# MCU.net
KiCad netlist of a schematic drawn in Altium Designer
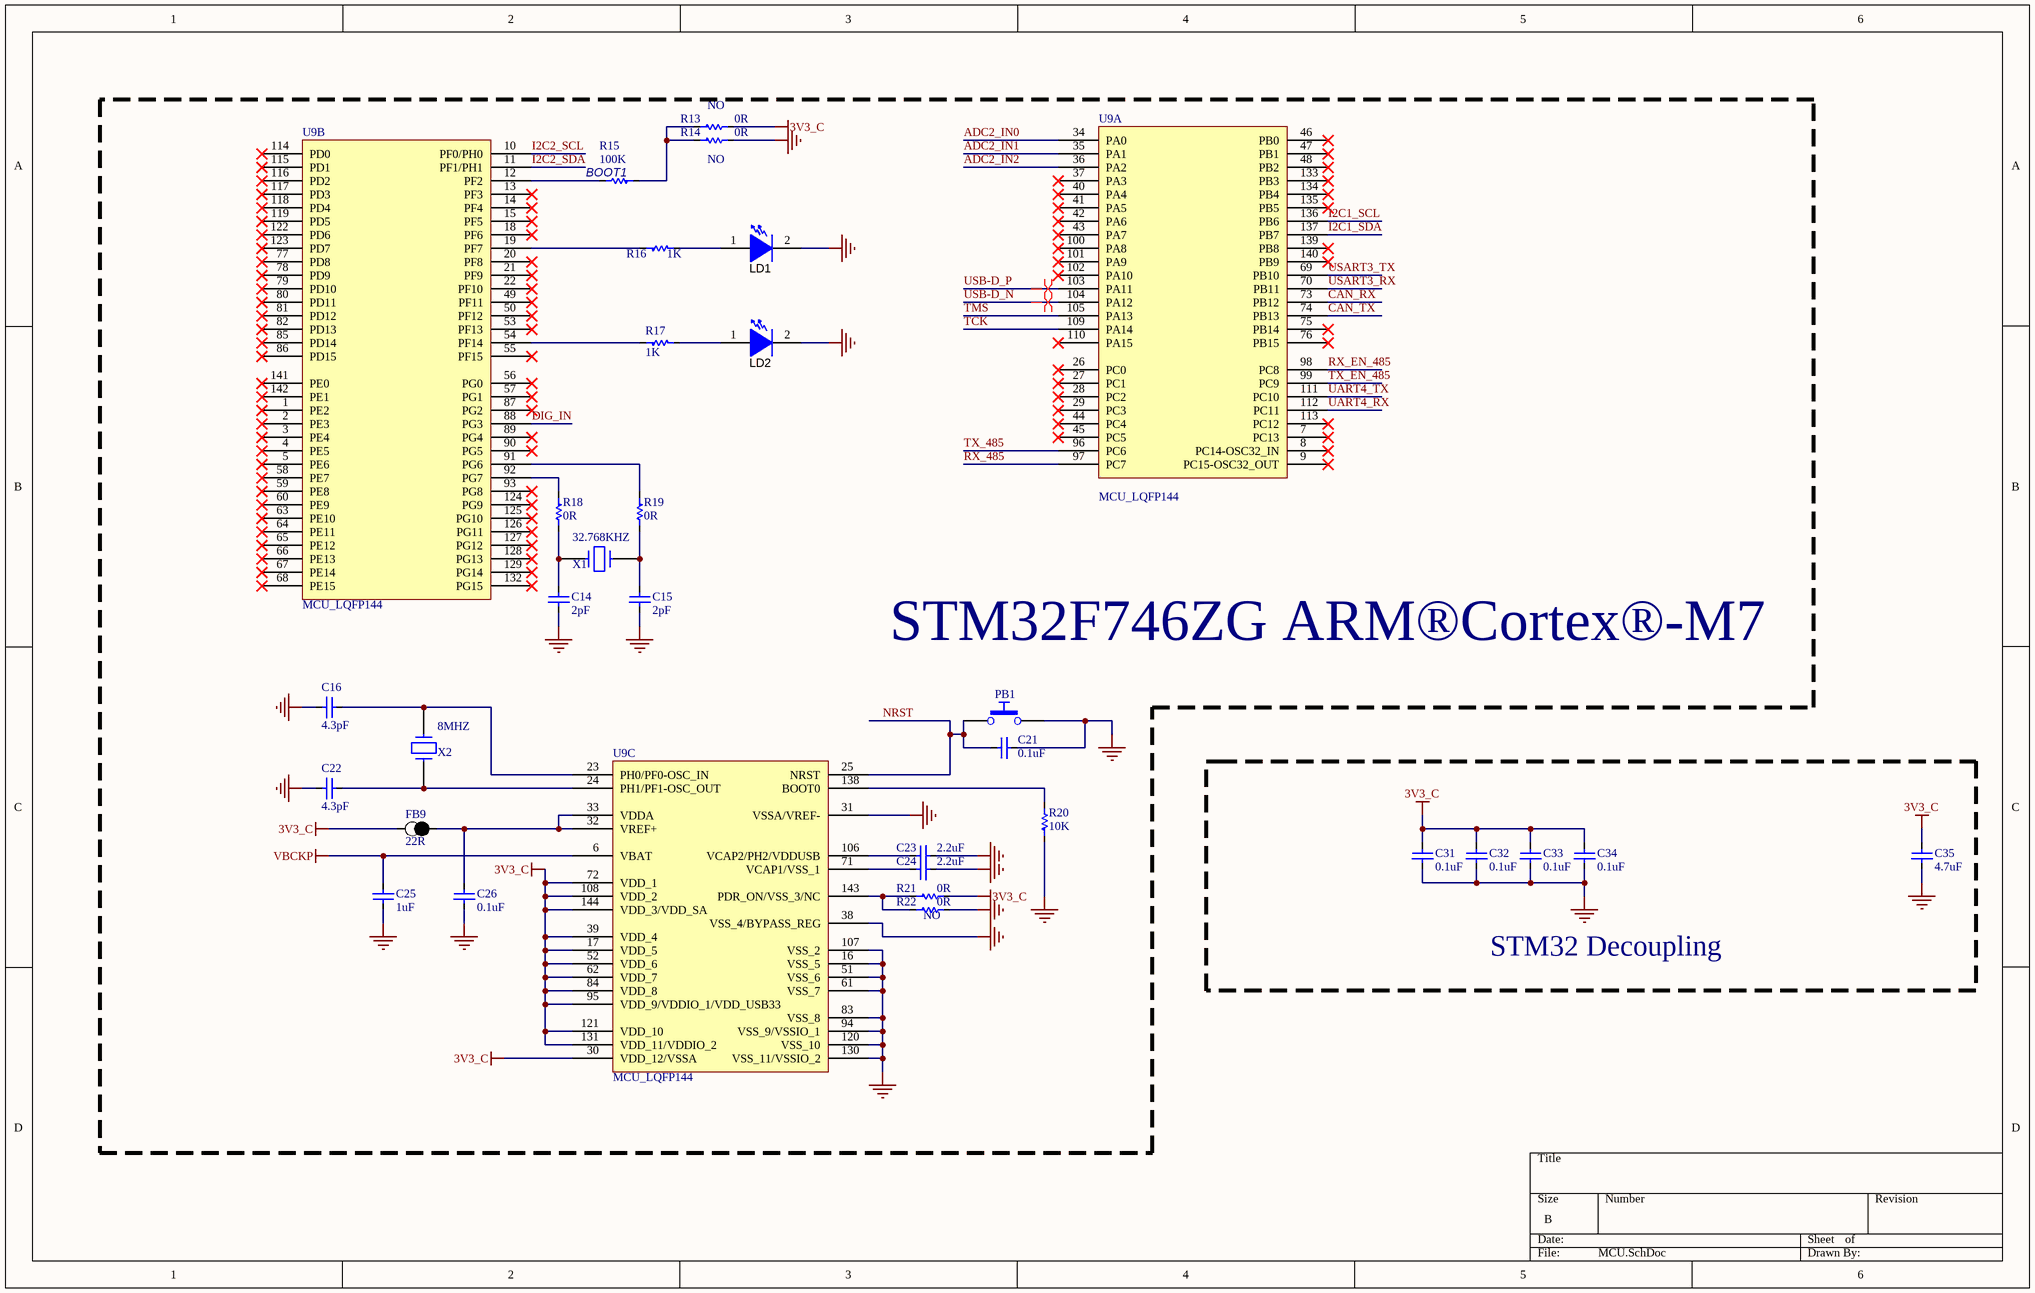
[diagram p0: MCU.SchDoc]

(export (version "E")
  (design (tool "Eeschema 10.0.6"))
  (components
    (comp (ref "C14")
      (value "2pF")
      (footprint "CAPC1608-0603X85N")
      (description "CAP CER 2PF 50V NPO 0603")
      (fields (field (name "MANUFACTURER") "Yageo") (field (name "VOLTAGE") "50V"))
      (libsource (lib "capacitor") (part "Capacitor Ceramic"))
    )
    (comp (ref "C15")
      (value "2pF")
      (footprint "CAPC1608-0603X85N")
      (description "CAP CER 2PF 50V NPO 0603")
      (fields (field (name "MANUFACTURER") "Yageo") (field (name "VOLTAGE") "50V"))
      (libsource (lib "capacitor") (part "Capacitor Ceramic"))
    )
    (comp (ref "C16")
      (value "4.3pF")
      (footprint "CAPC1005-0402X55N")
      (description "CAP CER 4.3PF 50V C0G/NPO 0402")
      (fields (field (name "MANUFACTURER") "Yageo") (field (name "VOLTAGE") "50V"))
      (libsource (lib "capacitor") (part "Capacitor Ceramic"))
    )
    (comp (ref "C21")
      (value "0.1uF")
      (footprint "CAPC1608-0603X85N")
      (description "CAP CER 0.1UF 25V X7R 0603")
      (fields (field (name "MANUFACTURER") "Yageo") (field (name "VOLTAGE") "25V"))
      (libsource (lib "capacitor") (part "Capacitor Ceramic"))
    )
    (comp (ref "C22")
      (value "4.3pF")
      (footprint "CAPC1005-0402X55N")
      (description "CAP CER 4.3PF 50V C0G/NPO 0402")
      (fields (field (name "MANUFACTURER") "Yageo") (field (name "VOLTAGE") "50V"))
      (libsource (lib "capacitor") (part "Capacitor Ceramic"))
    )
    (comp (ref "C23")
      (value "2.2uF")
      (footprint "CAPC2012-0805X80N")
      (description "CAP CER 2.2UF 16V X7R 0805")
      (fields (field (name "VOLTAGE") "16V") (field (name "TOLERANCE") "±10%"))
      (libsource (lib "capacitor") (part "Capacitor Ceramic"))
    )
    (comp (ref "C24")
      (value "2.2uF")
      (footprint "CAPC2012-0805X80N")
      (description "CAP CER 2.2UF 16V X7R 0805")
      (fields (field (name "VOLTAGE") "16V") (field (name "TOLERANCE") "±10%"))
      (libsource (lib "capacitor") (part "Capacitor Ceramic"))
    )
    (comp (ref "C25")
      (value "1uF")
      (footprint "CAPC1608-0603X85N")
      (description "CAP CER 1UF 25V X5R 0603")
      (fields (field (name "MANUFACTURER") "Samsung Electro-Mechanics") (field (name "VOLTAGE") "25V"))
      (libsource (lib "capacitor") (part "Capacitor Ceramic"))
    )
    (comp (ref "C26")
      (value "0.1uF")
      (footprint "CAPC1608-0603X85N")
      (description "CAP CER 0.1UF 25V X7R 0603")
      (fields (field (name "MANUFACTURER") "Yageo") (field (name "VOLTAGE") "25V"))
      (libsource (lib "capacitor") (part "Capacitor Ceramic"))
    )
    (comp (ref "C31")
      (value "0.1uF")
      (footprint "CAPC1608-0603X85N")
      (description "CAP CER 0.1UF 25V X7R 0603")
      (fields (field (name "MANUFACTURER") "Yageo") (field (name "VOLTAGE") "25V"))
      (libsource (lib "capacitor") (part "Capacitor Ceramic"))
    )
    (comp (ref "C32")
      (value "0.1uF")
      (footprint "CAPC1608-0603X85N")
      (description "CAP CER 0.1UF 25V X7R 0603")
      (fields (field (name "MANUFACTURER") "Yageo") (field (name "VOLTAGE") "25V"))
      (libsource (lib "capacitor") (part "Capacitor Ceramic"))
    )
    (comp (ref "C33")
      (value "0.1uF")
      (footprint "CAPC1608-0603X85N")
      (description "CAP CER 0.1UF 25V X7R 0603")
      (fields (field (name "MANUFACTURER") "Yageo") (field (name "VOLTAGE") "25V"))
      (libsource (lib "capacitor") (part "Capacitor Ceramic"))
    )
    (comp (ref "C34")
      (value "0.1uF")
      (footprint "CAPC1608-0603X85N")
      (description "CAP CER 0.1UF 25V X7R 0603")
      (fields (field (name "MANUFACTURER") "Yageo") (field (name "VOLTAGE") "25V"))
      (libsource (lib "capacitor") (part "Capacitor Ceramic"))
    )
    (comp (ref "C35")
      (value "4.7uF")
      (footprint "CAPC1608-0603X85N")
      (description "CAP CER 4.7UF 16V X5R 0603")
      (fields (field (name "MANUFACTURER") "Yageo") (field (name "VOLTAGE") "16V"))
      (libsource (lib "capacitor") (part "Capacitor Ceramic"))
    )
    (comp (ref "FB9")
      (value "22R")
      (footprint "INDC1608-0603X50N")
      (description "FERRITE BEAD 22 OHM 0805 1LN")
      (fields (field (name "MANUFACTURER") "Würth") (field (name "TOLERANCE") "-55°C ~ 125°C"))
      (libsource (lib "Inductors & Transformers") (part "Inductor EMI suppresion"))
    )
    (comp (ref "LD1")
      (value "160-1183-1-ND")
      (footprint "LED_LTST-C190")
      (description "LED, Green, SMD")
      (libsource (lib "LED") (part "LTST-C190GKT"))
    )
    (comp (ref "LD2")
      (value "160-1183-1-ND")
      (footprint "LED_LTST-C190")
      (description "LED, Green, SMD")
      (libsource (lib "LED") (part "LTST-C190GKT"))
    )
    (comp (ref "PB1")
      (value "Push Button")
      (footprint "PB_TYCO_FSMSM")
      (description "Push-Button Switch SPDT")
      (fields
        (field (name "PART NUMBER") "PB_TYCO_FSMSM")
        (field (name "MANUFACTURER") "TYCO ELECTRONICS")
        (field (name "AUTHOR") "CERN DEM JLC")
      )
      (libsource (lib "Eletro-mechanical") (part "PB SPST 1NO-2NO"))
    )
    (comp (ref "R13")
      (value "0R")
      (footprint "RESC1608-0603X50N")
      (description "RES SMD 0 OHM JUMPER 1/10W 0603")
      (fields
        (field (name "POPULATED") "NO")
        (field (name "MANUFACTURER") "Yageo")
        (field (name "TOLERANCE") "±1%")
      )
      (libsource (lib "resistor") (part "Resistor SMD"))
    )
    (comp (ref "R14")
      (value "0R")
      (footprint "RESC1608-0603X50N")
      (description "RES SMD 0 OHM JUMPER 1/10W 0603")
      (fields
        (field (name "POPULATED") "NO")
        (field (name "MANUFACTURER") "Yageo")
        (field (name "TOLERANCE") "±1%")
      )
      (libsource (lib "resistor") (part "Resistor SMD"))
    )
    (comp (ref "R15")
      (value "100K")
      (footprint "RESC1608-0603X50N")
      (description "RES SMD 100K OHM 1% 1/10W 0603")
      (fields (field (name "MANUFACTURER") "Panasonic Electronic Components") (field (name "TOLERANCE") "1%"))
      (libsource (lib "resistor") (part "Resistor SMD"))
    )
    (comp (ref "R16")
      (value "1K")
      (footprint "RESC1608-0603X50N")
      (description "RES SMD 1K OHM 1% 1/10W 0603")
      (fields (field (name "MANUFACTURER") "Panasonic Electronic Components") (field (name "TOLERANCE") "1%"))
      (libsource (lib "resistor") (part "Resistor SMD"))
    )
    (comp (ref "R17")
      (value "1K")
      (footprint "RESC1608-0603X50N")
      (description "RES SMD 1K OHM 1% 1/10W 0603")
      (fields (field (name "MANUFACTURER") "Panasonic Electronic Components") (field (name "TOLERANCE") "1%"))
      (libsource (lib "resistor") (part "Resistor SMD"))
    )
    (comp (ref "R18")
      (value "0R")
      (footprint "RESC1608-0603X50N")
      (description "RES SMD 0 OHM JUMPER 1/10W 0603")
      (fields (field (name "MANUFACTURER") "Yageo") (field (name "TOLERANCE") "±1%"))
      (libsource (lib "resistor") (part "Resistor SMD"))
    )
    (comp (ref "R19")
      (value "0R")
      (footprint "RESC1608-0603X50N")
      (description "RES SMD 0 OHM JUMPER 1/10W 0603")
      (fields (field (name "MANUFACTURER") "Yageo") (field (name "TOLERANCE") "±1%"))
      (libsource (lib "resistor") (part "Resistor SMD"))
    )
    (comp (ref "R20")
      (value "10K")
      (footprint "RESC1608-0603X50N")
      (description "RES SMD 10K OHM 1% 1/10W 0603")
      (fields (field (name "MANUFACTURER") "Yageo") (field (name "TOLERANCE") "±1%"))
      (libsource (lib "resistor") (part "Resistor SMD"))
    )
    (comp (ref "R21")
      (value "0R")
      (footprint "RESC1608-0603X50N")
      (description "RES SMD 0 OHM JUMPER 1/10W 0603")
      (fields (field (name "MANUFACTURER") "Yageo") (field (name "TOLERANCE") "±1%"))
      (libsource (lib "resistor") (part "Resistor SMD"))
    )
    (comp (ref "R22")
      (value "0R")
      (footprint "RESC1608-0603X50N")
      (description "RES SMD 0 OHM JUMPER 1/10W 0603")
      (fields
        (field (name "POPULATED") "NO")
        (field (name "MANUFACTURER") "Yageo")
        (field (name "TOLERANCE") "±1%")
      )
      (libsource (lib "resistor") (part "Resistor SMD"))
    )
    (comp (ref "U9")
      (value "MCU_LQFP144")
      (footprint "QFP50P2200X2200X160-144N")
      (fields (field (name "MANUFACTURER") "STMicroelectronics") (field (name "VOLTAGE") "1.8V - 3.6V"))
      (libsource (lib "MB1137") (part "MCU_LQFP144"))
    )
    (comp (ref "X1")
      (value "32.768KHZ")
      (footprint "2-SMD")
      (description "32.768kHz  Crystal 6pF 70 kOhms 2-SMD, No Lead")
      (fields (field (name "MANUFACTURER") "NDK America, Inc.") (field (name "TOLERANCE") "6pF, 70 kOhms"))
      (libsource (lib "MB1167") (part "CRYSTAL_32K"))
    )
    (comp (ref "X2")
      (value "8MHZ")
      (footprint "2-SMD")
      (description "CRYSTAL 8MHZ 8PF SMD")
      (fields (field (name "MANUFACTURER") "NDK America, Inc.") (field (name "TOLERANCE") "6pF, 70 kOhms"))
      (libsource (lib "MB1167") (part "CRYSTAL_32K"))
    )
  )
  (nets
    (net (code "1") (name "/ADC2_IN0") (class "Default")
      (node (ref "U9") (pin "34") (pinfunction "PA0_34") (pintype "passive"))
    )
    (net (code "2") (name "/ADC2_IN1") (class "Default")
      (node (ref "U9") (pin "35") (pinfunction "PA1_35") (pintype "passive"))
    )
    (net (code "3") (name "/ADC2_IN2") (class "Default")
      (node (ref "U9") (pin "36") (pinfunction "PA2_36") (pintype "passive"))
    )
    (net (code "4") (name "/CAN_RX") (class "Default")
      (node (ref "U9") (pin "73") (pinfunction "PB12_73") (pintype "passive"))
    )
    (net (code "5") (name "/CAN_TX") (class "Default")
      (node (ref "U9") (pin "74") (pinfunction "PB13_74") (pintype "passive"))
    )
    (net (code "6") (name "/DIG_IN") (class "Default")
      (node (ref "U9") (pin "88") (pinfunction "PG3_88") (pintype "passive"))
    )
    (net (code "7") (name "/I2C1_SCL") (class "Default")
      (node (ref "U9") (pin "136") (pinfunction "PB6_136") (pintype "passive"))
    )
    (net (code "8") (name "/I2C1_SDA") (class "Default")
      (node (ref "U9") (pin "137") (pinfunction "PB7_137") (pintype "passive"))
    )
    (net (code "9") (name "/I2C2_SCL") (class "Default")
      (node (ref "U9") (pin "10") (pinfunction "PF0/PH0_10") (pintype "passive"))
    )
    (net (code "10") (name "/I2C2_SDA") (class "Default")
      (node (ref "U9") (pin "11") (pinfunction "PF1/PH1_11") (pintype "passive"))
    )
    (net (code "11") (name "/NRST") (class "Default")
      (node (ref "C21") (pin "1") (pinfunction "1_1") (pintype "passive"))
      (node (ref "PB1") (pin "1") (pinfunction "1_1") (pintype "passive"))
      (node (ref "U9") (pin "25") (pinfunction "NRST_25") (pintype "passive"))
    )
    (net (code "12") (name "/RX_485") (class "Default")
      (node (ref "U9") (pin "97") (pinfunction "PC7_97") (pintype "passive"))
    )
    (net (code "13") (name "/RX_EN_485") (class "Default")
      (node (ref "U9") (pin "98") (pinfunction "PC8_98") (pintype "passive"))
    )
    (net (code "14") (name "/TCK") (class "Default")
      (node (ref "U9") (pin "109") (pinfunction "PA14_109") (pintype "passive"))
    )
    (net (code "15") (name "/TMS") (class "Default")
      (node (ref "U9") (pin "105") (pinfunction "PA13_105") (pintype "passive"))
    )
    (net (code "16") (name "/TX_485") (class "Default")
      (node (ref "U9") (pin "96") (pinfunction "PC6_96") (pintype "passive"))
    )
    (net (code "17") (name "/TX_EN_485") (class "Default")
      (node (ref "U9") (pin "99") (pinfunction "PC9_99") (pintype "passive"))
    )
    (net (code "18") (name "/UART4_RX") (class "Default")
      (node (ref "U9") (pin "112") (pinfunction "PC11_112") (pintype "passive"))
    )
    (net (code "19") (name "/UART4_TX") (class "Default")
      (node (ref "U9") (pin "111") (pinfunction "PC10_111") (pintype "passive"))
    )
    (net (code "20") (name "/USART3_RX") (class "Default")
      (node (ref "U9") (pin "70") (pinfunction "PB11_70") (pintype "passive"))
    )
    (net (code "21") (name "/USART3_TX") (class "Default")
      (node (ref "U9") (pin "69") (pinfunction "PB10_69") (pintype "passive"))
    )
    (net (code "22") (name "/USB-D_N") (class "Default")
      (node (ref "U9") (pin "104") (pinfunction "PA12_104") (pintype "passive"))
    )
    (net (code "23") (name "/USB-D_P") (class "Default")
      (node (ref "U9") (pin "103") (pinfunction "PA11_103") (pintype "passive"))
    )
    (net (code "24") (name "3V3_C") (class "Default")
      (node (ref "C31") (pin "1") (pinfunction "1_1") (pintype "passive"))
      (node (ref "C32") (pin "1") (pinfunction "1_1") (pintype "passive"))
      (node (ref "C33") (pin "1") (pinfunction "1_1") (pintype "passive"))
      (node (ref "C34") (pin "1") (pinfunction "1_1") (pintype "passive"))
      (node (ref "C35") (pin "1") (pinfunction "1_1") (pintype "passive"))
      (node (ref "FB9") (pin "2") (pinfunction "2_2") (pintype "passive"))
      (node (ref "R13") (pin "2") (pinfunction "2_2") (pintype "passive"))
      (node (ref "R21") (pin "2") (pinfunction "2_2") (pintype "passive"))
      (node (ref "U9") (pin "108") (pinfunction "VDD_2_108") (pintype "passive"))
      (node (ref "U9") (pin "121") (pinfunction "VDD_10_121") (pintype "passive"))
      (node (ref "U9") (pin "131") (pinfunction "VDD_11/VDDIO_2_131") (pintype "passive"))
      (node (ref "U9") (pin "144") (pinfunction "VDD_3/VDD_SA_144") (pintype "passive"))
      (node (ref "U9") (pin "17") (pinfunction "VDD_5_17") (pintype "passive"))
      (node (ref "U9") (pin "30") (pinfunction "VDD_12/VSSA_30") (pintype "passive"))
      (node (ref "U9") (pin "39") (pinfunction "VDD_4_39") (pintype "passive"))
      (node (ref "U9") (pin "52") (pinfunction "VDD_6_52") (pintype "passive"))
      (node (ref "U9") (pin "62") (pinfunction "VDD_7_62") (pintype "passive"))
      (node (ref "U9") (pin "72") (pinfunction "VDD_1_72") (pintype "passive"))
      (node (ref "U9") (pin "84") (pinfunction "VDD_8_84") (pintype "passive"))
      (node (ref "U9") (pin "95") (pinfunction "VDD_9/VDDIO_1/VDD_USB33_95") (pintype "passive"))
    )
    (net (code "25") (name "GND") (class "Default")
      (node (ref "C14") (pin "2") (pinfunction "2_2") (pintype "passive"))
      (node (ref "C15") (pin "2") (pinfunction "2_2") (pintype "passive"))
      (node (ref "C16") (pin "2") (pinfunction "2_2") (pintype "passive"))
      (node (ref "C21") (pin "2") (pinfunction "2_2") (pintype "passive"))
      (node (ref "C22") (pin "2") (pinfunction "2_2") (pintype "passive"))
      (node (ref "C23") (pin "2") (pinfunction "2_2") (pintype "passive"))
      (node (ref "C24") (pin "2") (pinfunction "2_2") (pintype "passive"))
      (node (ref "C25") (pin "1") (pinfunction "1_1") (pintype "passive"))
      (node (ref "C26") (pin "2") (pinfunction "2_2") (pintype "passive"))
      (node (ref "C31") (pin "2") (pinfunction "2_2") (pintype "passive"))
      (node (ref "C32") (pin "2") (pinfunction "2_2") (pintype "passive"))
      (node (ref "C33") (pin "2") (pinfunction "2_2") (pintype "passive"))
      (node (ref "C34") (pin "2") (pinfunction "2_2") (pintype "passive"))
      (node (ref "C35") (pin "2") (pinfunction "2_2") (pintype "passive"))
      (node (ref "LD1") (pin "2") (pinfunction "K_2") (pintype "passive"))
      (node (ref "LD2") (pin "2") (pinfunction "K_2") (pintype "passive"))
      (node (ref "PB1") (pin "2") (pinfunction "2_2") (pintype "passive"))
      (node (ref "R14") (pin "2") (pinfunction "2_2") (pintype "passive"))
      (node (ref "R20") (pin "1") (pinfunction "1_1") (pintype "passive"))
      (node (ref "R22") (pin "2") (pinfunction "2_2") (pintype "passive"))
      (node (ref "U9") (pin "107") (pinfunction "VSS_2_107") (pintype "passive"))
      (node (ref "U9") (pin "120") (pinfunction "VSS_10_120") (pintype "passive"))
      (node (ref "U9") (pin "130") (pinfunction "VSS_11/VSSIO_2_130") (pintype "passive"))
      (node (ref "U9") (pin "16") (pinfunction "VSS_5_16") (pintype "passive"))
      (node (ref "U9") (pin "31") (pinfunction "VSSA/VREF-_31") (pintype "passive"))
      (node (ref "U9") (pin "38") (pinfunction "VSS_4/BYPASS_REG_38") (pintype "passive"))
      (node (ref "U9") (pin "51") (pinfunction "VSS_6_51") (pintype "passive"))
      (node (ref "U9") (pin "61") (pinfunction "VSS_7_61") (pintype "passive"))
      (node (ref "U9") (pin "83") (pinfunction "VSS_8_83") (pintype "passive"))
      (node (ref "U9") (pin "94") (pinfunction "VSS_9/VSSIO_1_94") (pintype "passive"))
    )
    (net (code "26") (name "Net-(C14-Pad1)") (class "Default")
      (node (ref "C14") (pin "1") (pinfunction "1_1") (pintype "passive"))
      (node (ref "R18") (pin "2") (pinfunction "2_2") (pintype "passive"))
      (node (ref "X1") (pin "1") (pinfunction "1_1") (pintype "passive"))
    )
    (net (code "27") (name "Net-(C15-Pad1)") (class "Default")
      (node (ref "C15") (pin "1") (pinfunction "1_1") (pintype "passive"))
      (node (ref "R19") (pin "2") (pinfunction "2_2") (pintype "passive"))
      (node (ref "X1") (pin "2") (pinfunction "2_2") (pintype "passive"))
    )
    (net (code "28") (name "Net-(LD1-A)") (class "Default")
      (node (ref "LD1") (pin "1") (pinfunction "A_1") (pintype "passive"))
      (node (ref "R16") (pin "2") (pinfunction "2_2") (pintype "passive"))
    )
    (net (code "29") (name "Net-(LD2-A)") (class "Default")
      (node (ref "LD2") (pin "1") (pinfunction "A_1") (pintype "passive"))
      (node (ref "R17") (pin "2") (pinfunction "2_2") (pintype "passive"))
    )
    (net (code "30") (name "Net-(R13-Pad1)") (class "Default")
      (node (ref "R13") (pin "1") (pinfunction "1_1") (pintype "passive"))
      (node (ref "R14") (pin "1") (pinfunction "1_1") (pintype "passive"))
      (node (ref "R15") (pin "1") (pinfunction "1_1") (pintype "passive"))
    )
    (net (code "31") (name "Net-(U9B-PF2)") (class "Default")
      (node (ref "R15") (pin "2") (pinfunction "2_2") (pintype "passive"))
      (node (ref "U9") (pin "12") (pinfunction "PF2_12") (pintype "passive"))
    )
    (net (code "32") (name "Net-(U9B-PF7)") (class "Default")
      (node (ref "R16") (pin "1") (pinfunction "1_1") (pintype "passive"))
      (node (ref "U9") (pin "19") (pinfunction "PF7_19") (pintype "passive"))
    )
    (net (code "33") (name "Net-(U9B-PF14)") (class "Default")
      (node (ref "R17") (pin "1") (pinfunction "1_1") (pintype "passive"))
      (node (ref "U9") (pin "54") (pinfunction "PF14_54") (pintype "passive"))
    )
    (net (code "34") (name "Net-(U9B-PG6)") (class "Default")
      (node (ref "R19") (pin "1") (pinfunction "1_1") (pintype "passive"))
      (node (ref "U9") (pin "91") (pinfunction "PG6_91") (pintype "passive"))
    )
    (net (code "35") (name "Net-(U9B-PG7)") (class "Default")
      (node (ref "R18") (pin "1") (pinfunction "1_1") (pintype "passive"))
      (node (ref "U9") (pin "92") (pinfunction "PG7_92") (pintype "passive"))
    )
    (net (code "36") (name "Net-(U9C-BOOT0)") (class "Default")
      (node (ref "R20") (pin "2") (pinfunction "2_2") (pintype "passive"))
      (node (ref "U9") (pin "138") (pinfunction "BOOT0_138") (pintype "passive"))
    )
    (net (code "37") (name "Net-(U9C-PDR_ON{slash}VSS_3{slash}NC)") (class "Default")
      (node (ref "R21") (pin "1") (pinfunction "1_1") (pintype "passive"))
      (node (ref "R22") (pin "1") (pinfunction "1_1") (pintype "passive"))
      (node (ref "U9") (pin "143") (pinfunction "PDR_ON/VSS_3/NC_143") (pintype "passive"))
    )
    (net (code "38") (name "Net-(U9C-PH0{slash}PF0-OSC_IN)") (class "Default")
      (node (ref "C16") (pin "1") (pinfunction "1_1") (pintype "passive"))
      (node (ref "U9") (pin "23") (pinfunction "PH0/PF0-OSC_IN_23") (pintype "passive"))
      (node (ref "X2") (pin "2") (pinfunction "2_2") (pintype "passive"))
    )
    (net (code "39") (name "Net-(U9C-PH1{slash}PF1-OSC_OUT)") (class "Default")
      (node (ref "C22") (pin "1") (pinfunction "1_1") (pintype "passive"))
      (node (ref "U9") (pin "24") (pinfunction "PH1/PF1-OSC_OUT_24") (pintype "passive"))
      (node (ref "X2") (pin "1") (pinfunction "1_1") (pintype "passive"))
    )
    (net (code "40") (name "Net-(U9C-VCAP1{slash}VSS_1)") (class "Default")
      (node (ref "C24") (pin "1") (pinfunction "1_1") (pintype "passive"))
      (node (ref "U9") (pin "71") (pinfunction "VCAP1/VSS_1_71") (pintype "passive"))
    )
    (net (code "41") (name "Net-(U9C-VCAP2{slash}PH2{slash}VDDUSB)") (class "Default")
      (node (ref "C23") (pin "1") (pinfunction "1_1") (pintype "passive"))
      (node (ref "U9") (pin "106") (pinfunction "VCAP2/PH2/VDDUSB_106") (pintype "passive"))
    )
    (net (code "42") (name "Net-(U9C-VDDA)") (class "Default")
      (node (ref "C26") (pin "1") (pinfunction "1_1") (pintype "passive"))
      (node (ref "FB9") (pin "1") (pinfunction "1_1") (pintype "passive"))
      (node (ref "U9") (pin "32") (pinfunction "VREF+_32") (pintype "passive"))
      (node (ref "U9") (pin "33") (pinfunction "VDDA_33") (pintype "passive"))
    )
    (net (code "43") (name "VBCKP") (class "Default")
      (node (ref "C25") (pin "2") (pinfunction "2_2") (pintype "passive"))
      (node (ref "U9") (pin "6") (pinfunction "VBAT_6") (pintype "passive"))
    )
    (net (code "44") (name "unconnected-(U9A-PA3-Pad37)") (class "Default")
      (node (ref "U9") (pin "37") (pinfunction "PA3_37") (pintype "passive+no_connect"))
    )
    (net (code "45") (name "unconnected-(U9A-PA4-Pad40)") (class "Default")
      (node (ref "U9") (pin "40") (pinfunction "PA4_40") (pintype "passive+no_connect"))
    )
    (net (code "46") (name "unconnected-(U9A-PA5-Pad41)") (class "Default")
      (node (ref "U9") (pin "41") (pinfunction "PA5_41") (pintype "passive+no_connect"))
    )
    (net (code "47") (name "unconnected-(U9A-PA6-Pad42)") (class "Default")
      (node (ref "U9") (pin "42") (pinfunction "PA6_42") (pintype "passive+no_connect"))
    )
    (net (code "48") (name "unconnected-(U9A-PA7-Pad43)") (class "Default")
      (node (ref "U9") (pin "43") (pinfunction "PA7_43") (pintype "passive+no_connect"))
    )
    (net (code "49") (name "unconnected-(U9A-PA8-Pad100)") (class "Default")
      (node (ref "U9") (pin "100") (pinfunction "PA8_100") (pintype "passive+no_connect"))
    )
    (net (code "50") (name "unconnected-(U9A-PA9-Pad101)") (class "Default")
      (node (ref "U9") (pin "101") (pinfunction "PA9_101") (pintype "passive+no_connect"))
    )
    (net (code "51") (name "unconnected-(U9A-PA10-Pad102)") (class "Default")
      (node (ref "U9") (pin "102") (pinfunction "PA10_102") (pintype "passive+no_connect"))
    )
    (net (code "52") (name "unconnected-(U9A-PA15-Pad110)") (class "Default")
      (node (ref "U9") (pin "110") (pinfunction "PA15_110") (pintype "passive+no_connect"))
    )
    (net (code "53") (name "unconnected-(U9A-PB0-Pad46)") (class "Default")
      (node (ref "U9") (pin "46") (pinfunction "PB0_46") (pintype "passive+no_connect"))
    )
    (net (code "54") (name "unconnected-(U9A-PB1-Pad47)") (class "Default")
      (node (ref "U9") (pin "47") (pinfunction "PB1_47") (pintype "passive+no_connect"))
    )
    (net (code "55") (name "unconnected-(U9A-PB2-Pad48)") (class "Default")
      (node (ref "U9") (pin "48") (pinfunction "PB2_48") (pintype "passive+no_connect"))
    )
    (net (code "56") (name "unconnected-(U9A-PB3-Pad133)") (class "Default")
      (node (ref "U9") (pin "133") (pinfunction "PB3_133") (pintype "passive+no_connect"))
    )
    (net (code "57") (name "unconnected-(U9A-PB4-Pad134)") (class "Default")
      (node (ref "U9") (pin "134") (pinfunction "PB4_134") (pintype "passive+no_connect"))
    )
    (net (code "58") (name "unconnected-(U9A-PB5-Pad135)") (class "Default")
      (node (ref "U9") (pin "135") (pinfunction "PB5_135") (pintype "passive+no_connect"))
    )
    (net (code "59") (name "unconnected-(U9A-PB8-Pad139)") (class "Default")
      (node (ref "U9") (pin "139") (pinfunction "PB8_139") (pintype "passive+no_connect"))
    )
    (net (code "60") (name "unconnected-(U9A-PB9-Pad140)") (class "Default")
      (node (ref "U9") (pin "140") (pinfunction "PB9_140") (pintype "passive+no_connect"))
    )
    (net (code "61") (name "unconnected-(U9A-PB14-Pad75)") (class "Default")
      (node (ref "U9") (pin "75") (pinfunction "PB14_75") (pintype "passive+no_connect"))
    )
    (net (code "62") (name "unconnected-(U9A-PB15-Pad76)") (class "Default")
      (node (ref "U9") (pin "76") (pinfunction "PB15_76") (pintype "passive+no_connect"))
    )
    (net (code "63") (name "unconnected-(U9A-PC0-Pad26)") (class "Default")
      (node (ref "U9") (pin "26") (pinfunction "PC0_26") (pintype "passive+no_connect"))
    )
    (net (code "64") (name "unconnected-(U9A-PC1-Pad27)") (class "Default")
      (node (ref "U9") (pin "27") (pinfunction "PC1_27") (pintype "passive+no_connect"))
    )
    (net (code "65") (name "unconnected-(U9A-PC2-Pad28)") (class "Default")
      (node (ref "U9") (pin "28") (pinfunction "PC2_28") (pintype "passive+no_connect"))
    )
    (net (code "66") (name "unconnected-(U9A-PC3-Pad29)") (class "Default")
      (node (ref "U9") (pin "29") (pinfunction "PC3_29") (pintype "passive+no_connect"))
    )
    (net (code "67") (name "unconnected-(U9A-PC4-Pad44)") (class "Default")
      (node (ref "U9") (pin "44") (pinfunction "PC4_44") (pintype "passive+no_connect"))
    )
    (net (code "68") (name "unconnected-(U9A-PC5-Pad45)") (class "Default")
      (node (ref "U9") (pin "45") (pinfunction "PC5_45") (pintype "passive+no_connect"))
    )
    (net (code "69") (name "unconnected-(U9A-PC12-Pad113)") (class "Default")
      (node (ref "U9") (pin "113") (pinfunction "PC12_113") (pintype "passive+no_connect"))
    )
    (net (code "70") (name "unconnected-(U9A-PC13-Pad7)") (class "Default")
      (node (ref "U9") (pin "7") (pinfunction "PC13_7") (pintype "passive+no_connect"))
    )
    (net (code "71") (name "unconnected-(U9A-PC14-OSC32_IN-Pad8)") (class "Default")
      (node (ref "U9") (pin "8") (pinfunction "PC14-OSC32_IN_8") (pintype "passive+no_connect"))
    )
    (net (code "72") (name "unconnected-(U9A-PC15-OSC32_OUT-Pad9)") (class "Default")
      (node (ref "U9") (pin "9") (pinfunction "PC15-OSC32_OUT_9") (pintype "passive+no_connect"))
    )
    (net (code "73") (name "unconnected-(U9B-PD0-Pad114)") (class "Default")
      (node (ref "U9") (pin "114") (pinfunction "PD0_114") (pintype "passive+no_connect"))
    )
    (net (code "74") (name "unconnected-(U9B-PD1-Pad115)") (class "Default")
      (node (ref "U9") (pin "115") (pinfunction "PD1_115") (pintype "passive+no_connect"))
    )
    (net (code "75") (name "unconnected-(U9B-PD2-Pad116)") (class "Default")
      (node (ref "U9") (pin "116") (pinfunction "PD2_116") (pintype "passive+no_connect"))
    )
    (net (code "76") (name "unconnected-(U9B-PD3-Pad117)") (class "Default")
      (node (ref "U9") (pin "117") (pinfunction "PD3_117") (pintype "passive+no_connect"))
    )
    (net (code "77") (name "unconnected-(U9B-PD4-Pad118)") (class "Default")
      (node (ref "U9") (pin "118") (pinfunction "PD4_118") (pintype "passive+no_connect"))
    )
    (net (code "78") (name "unconnected-(U9B-PD5-Pad119)") (class "Default")
      (node (ref "U9") (pin "119") (pinfunction "PD5_119") (pintype "passive+no_connect"))
    )
    (net (code "79") (name "unconnected-(U9B-PD6-Pad122)") (class "Default")
      (node (ref "U9") (pin "122") (pinfunction "PD6_122") (pintype "passive+no_connect"))
    )
    (net (code "80") (name "unconnected-(U9B-PD7-Pad123)") (class "Default")
      (node (ref "U9") (pin "123") (pinfunction "PD7_123") (pintype "passive+no_connect"))
    )
    (net (code "81") (name "unconnected-(U9B-PD8-Pad77)") (class "Default")
      (node (ref "U9") (pin "77") (pinfunction "PD8_77") (pintype "passive+no_connect"))
    )
    (net (code "82") (name "unconnected-(U9B-PD9-Pad78)") (class "Default")
      (node (ref "U9") (pin "78") (pinfunction "PD9_78") (pintype "passive+no_connect"))
    )
    (net (code "83") (name "unconnected-(U9B-PD10-Pad79)") (class "Default")
      (node (ref "U9") (pin "79") (pinfunction "PD10_79") (pintype "passive+no_connect"))
    )
    (net (code "84") (name "unconnected-(U9B-PD11-Pad80)") (class "Default")
      (node (ref "U9") (pin "80") (pinfunction "PD11_80") (pintype "passive+no_connect"))
    )
    (net (code "85") (name "unconnected-(U9B-PD12-Pad81)") (class "Default")
      (node (ref "U9") (pin "81") (pinfunction "PD12_81") (pintype "passive+no_connect"))
    )
    (net (code "86") (name "unconnected-(U9B-PD13-Pad82)") (class "Default")
      (node (ref "U9") (pin "82") (pinfunction "PD13_82") (pintype "passive+no_connect"))
    )
    (net (code "87") (name "unconnected-(U9B-PD14-Pad85)") (class "Default")
      (node (ref "U9") (pin "85") (pinfunction "PD14_85") (pintype "passive+no_connect"))
    )
    (net (code "88") (name "unconnected-(U9B-PD15-Pad86)") (class "Default")
      (node (ref "U9") (pin "86") (pinfunction "PD15_86") (pintype "passive+no_connect"))
    )
    (net (code "89") (name "unconnected-(U9B-PE0-Pad141)") (class "Default")
      (node (ref "U9") (pin "141") (pinfunction "PE0_141") (pintype "passive+no_connect"))
    )
    (net (code "90") (name "unconnected-(U9B-PE1-Pad142)") (class "Default")
      (node (ref "U9") (pin "142") (pinfunction "PE1_142") (pintype "passive+no_connect"))
    )
    (net (code "91") (name "unconnected-(U9B-PE2-Pad1)") (class "Default")
      (node (ref "U9") (pin "1") (pinfunction "PE2_1") (pintype "passive+no_connect"))
    )
    (net (code "92") (name "unconnected-(U9B-PE3-Pad2)") (class "Default")
      (node (ref "U9") (pin "2") (pinfunction "PE3_2") (pintype "passive+no_connect"))
    )
    (net (code "93") (name "unconnected-(U9B-PE4-Pad3)") (class "Default")
      (node (ref "U9") (pin "3") (pinfunction "PE4_3") (pintype "passive+no_connect"))
    )
    (net (code "94") (name "unconnected-(U9B-PE5-Pad4)") (class "Default")
      (node (ref "U9") (pin "4") (pinfunction "PE5_4") (pintype "passive+no_connect"))
    )
    (net (code "95") (name "unconnected-(U9B-PE6-Pad5)") (class "Default")
      (node (ref "U9") (pin "5") (pinfunction "PE6_5") (pintype "passive+no_connect"))
    )
    (net (code "96") (name "unconnected-(U9B-PE7-Pad58)") (class "Default")
      (node (ref "U9") (pin "58") (pinfunction "PE7_58") (pintype "passive+no_connect"))
    )
    (net (code "97") (name "unconnected-(U9B-PE8-Pad59)") (class "Default")
      (node (ref "U9") (pin "59") (pinfunction "PE8_59") (pintype "passive+no_connect"))
    )
    (net (code "98") (name "unconnected-(U9B-PE9-Pad60)") (class "Default")
      (node (ref "U9") (pin "60") (pinfunction "PE9_60") (pintype "passive+no_connect"))
    )
    (net (code "99") (name "unconnected-(U9B-PE10-Pad63)") (class "Default")
      (node (ref "U9") (pin "63") (pinfunction "PE10_63") (pintype "passive+no_connect"))
    )
    (net (code "100") (name "unconnected-(U9B-PE11-Pad64)") (class "Default")
      (node (ref "U9") (pin "64") (pinfunction "PE11_64") (pintype "passive+no_connect"))
    )
    (net (code "101") (name "unconnected-(U9B-PE12-Pad65)") (class "Default")
      (node (ref "U9") (pin "65") (pinfunction "PE12_65") (pintype "passive+no_connect"))
    )
    (net (code "102") (name "unconnected-(U9B-PE13-Pad66)") (class "Default")
      (node (ref "U9") (pin "66") (pinfunction "PE13_66") (pintype "passive+no_connect"))
    )
    (net (code "103") (name "unconnected-(U9B-PE14-Pad67)") (class "Default")
      (node (ref "U9") (pin "67") (pinfunction "PE14_67") (pintype "passive+no_connect"))
    )
    (net (code "104") (name "unconnected-(U9B-PE15-Pad68)") (class "Default")
      (node (ref "U9") (pin "68") (pinfunction "PE15_68") (pintype "passive+no_connect"))
    )
    (net (code "105") (name "unconnected-(U9B-PF3-Pad13)") (class "Default")
      (node (ref "U9") (pin "13") (pinfunction "PF3_13") (pintype "passive+no_connect"))
    )
    (net (code "106") (name "unconnected-(U9B-PF4-Pad14)") (class "Default")
      (node (ref "U9") (pin "14") (pinfunction "PF4_14") (pintype "passive+no_connect"))
    )
    (net (code "107") (name "unconnected-(U9B-PF5-Pad15)") (class "Default")
      (node (ref "U9") (pin "15") (pinfunction "PF5_15") (pintype "passive+no_connect"))
    )
    (net (code "108") (name "unconnected-(U9B-PF6-Pad18)") (class "Default")
      (node (ref "U9") (pin "18") (pinfunction "PF6_18") (pintype "passive+no_connect"))
    )
    (net (code "109") (name "unconnected-(U9B-PF8-Pad20)") (class "Default")
      (node (ref "U9") (pin "20") (pinfunction "PF8_20") (pintype "passive+no_connect"))
    )
    (net (code "110") (name "unconnected-(U9B-PF9-Pad21)") (class "Default")
      (node (ref "U9") (pin "21") (pinfunction "PF9_21") (pintype "passive+no_connect"))
    )
    (net (code "111") (name "unconnected-(U9B-PF10-Pad22)") (class "Default")
      (node (ref "U9") (pin "22") (pinfunction "PF10_22") (pintype "passive+no_connect"))
    )
    (net (code "112") (name "unconnected-(U9B-PF11-Pad49)") (class "Default")
      (node (ref "U9") (pin "49") (pinfunction "PF11_49") (pintype "passive+no_connect"))
    )
    (net (code "113") (name "unconnected-(U9B-PF12-Pad50)") (class "Default")
      (node (ref "U9") (pin "50") (pinfunction "PF12_50") (pintype "passive+no_connect"))
    )
    (net (code "114") (name "unconnected-(U9B-PF13-Pad53)") (class "Default")
      (node (ref "U9") (pin "53") (pinfunction "PF13_53") (pintype "passive+no_connect"))
    )
    (net (code "115") (name "unconnected-(U9B-PF15-Pad55)") (class "Default")
      (node (ref "U9") (pin "55") (pinfunction "PF15_55") (pintype "passive+no_connect"))
    )
    (net (code "116") (name "unconnected-(U9B-PG0-Pad56)") (class "Default")
      (node (ref "U9") (pin "56") (pinfunction "PG0_56") (pintype "passive+no_connect"))
    )
    (net (code "117") (name "unconnected-(U9B-PG1-Pad57)") (class "Default")
      (node (ref "U9") (pin "57") (pinfunction "PG1_57") (pintype "passive+no_connect"))
    )
    (net (code "118") (name "unconnected-(U9B-PG2-Pad87)") (class "Default")
      (node (ref "U9") (pin "87") (pinfunction "PG2_87") (pintype "passive+no_connect"))
    )
    (net (code "119") (name "unconnected-(U9B-PG4-Pad89)") (class "Default")
      (node (ref "U9") (pin "89") (pinfunction "PG4_89") (pintype "passive+no_connect"))
    )
    (net (code "120") (name "unconnected-(U9B-PG5-Pad90)") (class "Default")
      (node (ref "U9") (pin "90") (pinfunction "PG5_90") (pintype "passive+no_connect"))
    )
    (net (code "121") (name "unconnected-(U9B-PG8-Pad93)") (class "Default")
      (node (ref "U9") (pin "93") (pinfunction "PG8_93") (pintype "passive+no_connect"))
    )
    (net (code "122") (name "unconnected-(U9B-PG9-Pad124)") (class "Default")
      (node (ref "U9") (pin "124") (pinfunction "PG9_124") (pintype "passive+no_connect"))
    )
    (net (code "123") (name "unconnected-(U9B-PG10-Pad125)") (class "Default")
      (node (ref "U9") (pin "125") (pinfunction "PG10_125") (pintype "passive+no_connect"))
    )
    (net (code "124") (name "unconnected-(U9B-PG11-Pad126)") (class "Default")
      (node (ref "U9") (pin "126") (pinfunction "PG11_126") (pintype "passive+no_connect"))
    )
    (net (code "125") (name "unconnected-(U9B-PG12-Pad127)") (class "Default")
      (node (ref "U9") (pin "127") (pinfunction "PG12_127") (pintype "passive+no_connect"))
    )
    (net (code "126") (name "unconnected-(U9B-PG13-Pad128)") (class "Default")
      (node (ref "U9") (pin "128") (pinfunction "PG13_128") (pintype "passive+no_connect"))
    )
    (net (code "127") (name "unconnected-(U9B-PG14-Pad129)") (class "Default")
      (node (ref "U9") (pin "129") (pinfunction "PG14_129") (pintype "passive+no_connect"))
    )
    (net (code "128") (name "unconnected-(U9B-PG15-Pad132)") (class "Default")
      (node (ref "U9") (pin "132") (pinfunction "PG15_132") (pintype "passive+no_connect"))
    )
  )
)
